# OGX360I-2CH_-_USB_PCB.net
KiCad netlist of a schematic drawn in EAGLE
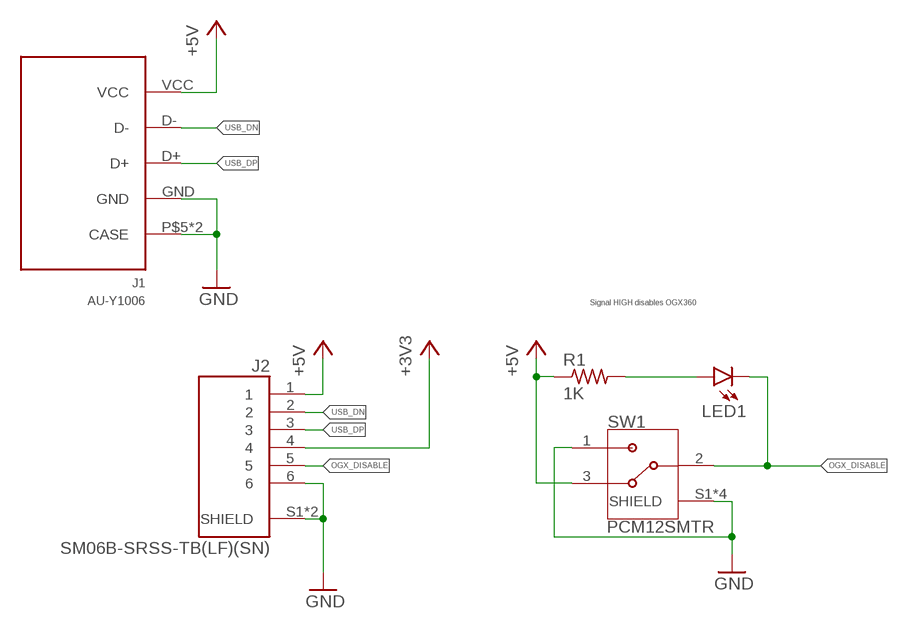
[diagram p0: schematic, sheet 1]

(export (version "E")
  (design (tool "Eeschema 10.0.6"))
  (components
    (comp (ref "J1")
      (value "AU-Y1006")
      (footprint "eagle-import:USBA_SMD")
      (fields (field (name "MF") "Assmann WSW"))
      (libsource (lib "eagle-import") (part "AU-Y1006"))
    )
    (comp (ref "J2")
      (value "SM06B-SRSS-TB(LF)(SN)")
      (footprint "eagle-import:JST_SM06B-SRSS-TB(LF)(SN)")
      (fields
        (field (name "DIGI-KEY_PART_NUMBER") "455-1806-1-ND")
        (field (name "MF") "JST Sales")
        (field (name "MP") "SM06B-SRSS-TB_LF__SN_")
      )
      (libsource (lib "eagle-import") (part "SM06B-SRSS-TB(LF)(SN)"))
    )
    (comp (ref "LED1")
      (value "LEDCHIP-LED0805")
      (footprint "eagle-import:CHIP-LED0805")
      (libsource (lib "eagle-import") (part "LEDCHIP-LED0805"))
    )
    (comp (ref "R1")
      (value "1K")
      (footprint "eagle-import:R0805")
      (libsource (lib "eagle-import") (part "R-US_R0805"))
    )
    (comp (ref "SW1")
      (value "PCM12SMTR")
      (footprint "eagle-import:SW_PCM12SMTR")
      (fields (field (name "DIGI-KEY_PART_NUMBER") "401-2016-1-ND") (field (name "MF") "C&K"))
      (libsource (lib "eagle-import") (part "PCM12SMTR"))
    )
  )
  (nets
    (net (code "1") (name "+3V3") (class "Default")
      (node (ref "J2") (pin "4") (pinfunction "4_4") (pintype "passive"))
    )
    (net (code "2") (name "+5V") (class "Default")
      (node (ref "J1") (pin "VCC") (pinfunction "VCC_VCC") (pintype "bidirectional"))
      (node (ref "J2") (pin "1") (pinfunction "1_1") (pintype "passive"))
      (node (ref "R1") (pin "1") (pinfunction "1_1") (pintype "passive"))
      (node (ref "SW1") (pin "3") (pinfunction "3_3") (pintype "passive"))
    )
    (net (code "3") (name "GND") (class "Default")
      (node (ref "J1") (pin "GND") (pinfunction "GND_GND") (pintype "bidirectional"))
      (node (ref "J1") (pin "P$5") (pinfunction "CASE_P$5") (pintype "bidirectional"))
      (node (ref "J1") (pin "P$6") (pinfunction "CASE_P$6") (pintype "bidirectional"))
      (node (ref "J2") (pin "6") (pinfunction "6_6") (pintype "passive"))
      (node (ref "J2") (pin "S1") (pinfunction "SHIELD_S1") (pintype "passive"))
      (node (ref "J2") (pin "S2") (pinfunction "SHIELD_S2") (pintype "passive"))
      (node (ref "SW1") (pin "1") (pinfunction "1_1") (pintype "passive"))
      (node (ref "SW1") (pin "S1") (pinfunction "SHIELD_S1") (pintype "passive"))
      (node (ref "SW1") (pin "S2") (pinfunction "SHIELD_S2") (pintype "passive"))
      (node (ref "SW1") (pin "S3") (pinfunction "SHIELD_S3") (pintype "passive"))
      (node (ref "SW1") (pin "S4") (pinfunction "SHIELD_S4") (pintype "passive"))
    )
    (net (code "4") (name "Net-(LED1-PadA)") (class "Default")
      (node (ref "LED1") (pin "A") (pinfunction "A_A") (pintype "passive"))
      (node (ref "R1") (pin "2") (pinfunction "2_2") (pintype "passive"))
    )
    (net (code "5") (name "OGX_DISABLE") (class "Default")
      (node (ref "J2") (pin "5") (pinfunction "5_5") (pintype "passive"))
      (node (ref "LED1") (pin "C") (pinfunction "C_C") (pintype "passive"))
      (node (ref "SW1") (pin "2") (pinfunction "2_2") (pintype "passive"))
    )
    (net (code "6") (name "USB_DN") (class "Default")
      (node (ref "J1") (pin "D-") (pinfunction "D-_D-") (pintype "bidirectional"))
      (node (ref "J2") (pin "2") (pinfunction "2_2") (pintype "passive"))
    )
    (net (code "7") (name "USB_DP") (class "Default")
      (node (ref "J1") (pin "D+") (pinfunction "D+_D+") (pintype "bidirectional"))
      (node (ref "J2") (pin "3") (pinfunction "3_3") (pintype "passive"))
    )
  )
)
